# EDAv0_2.net
KiCad netlist of a schematic drawn in EasyEDA Pro
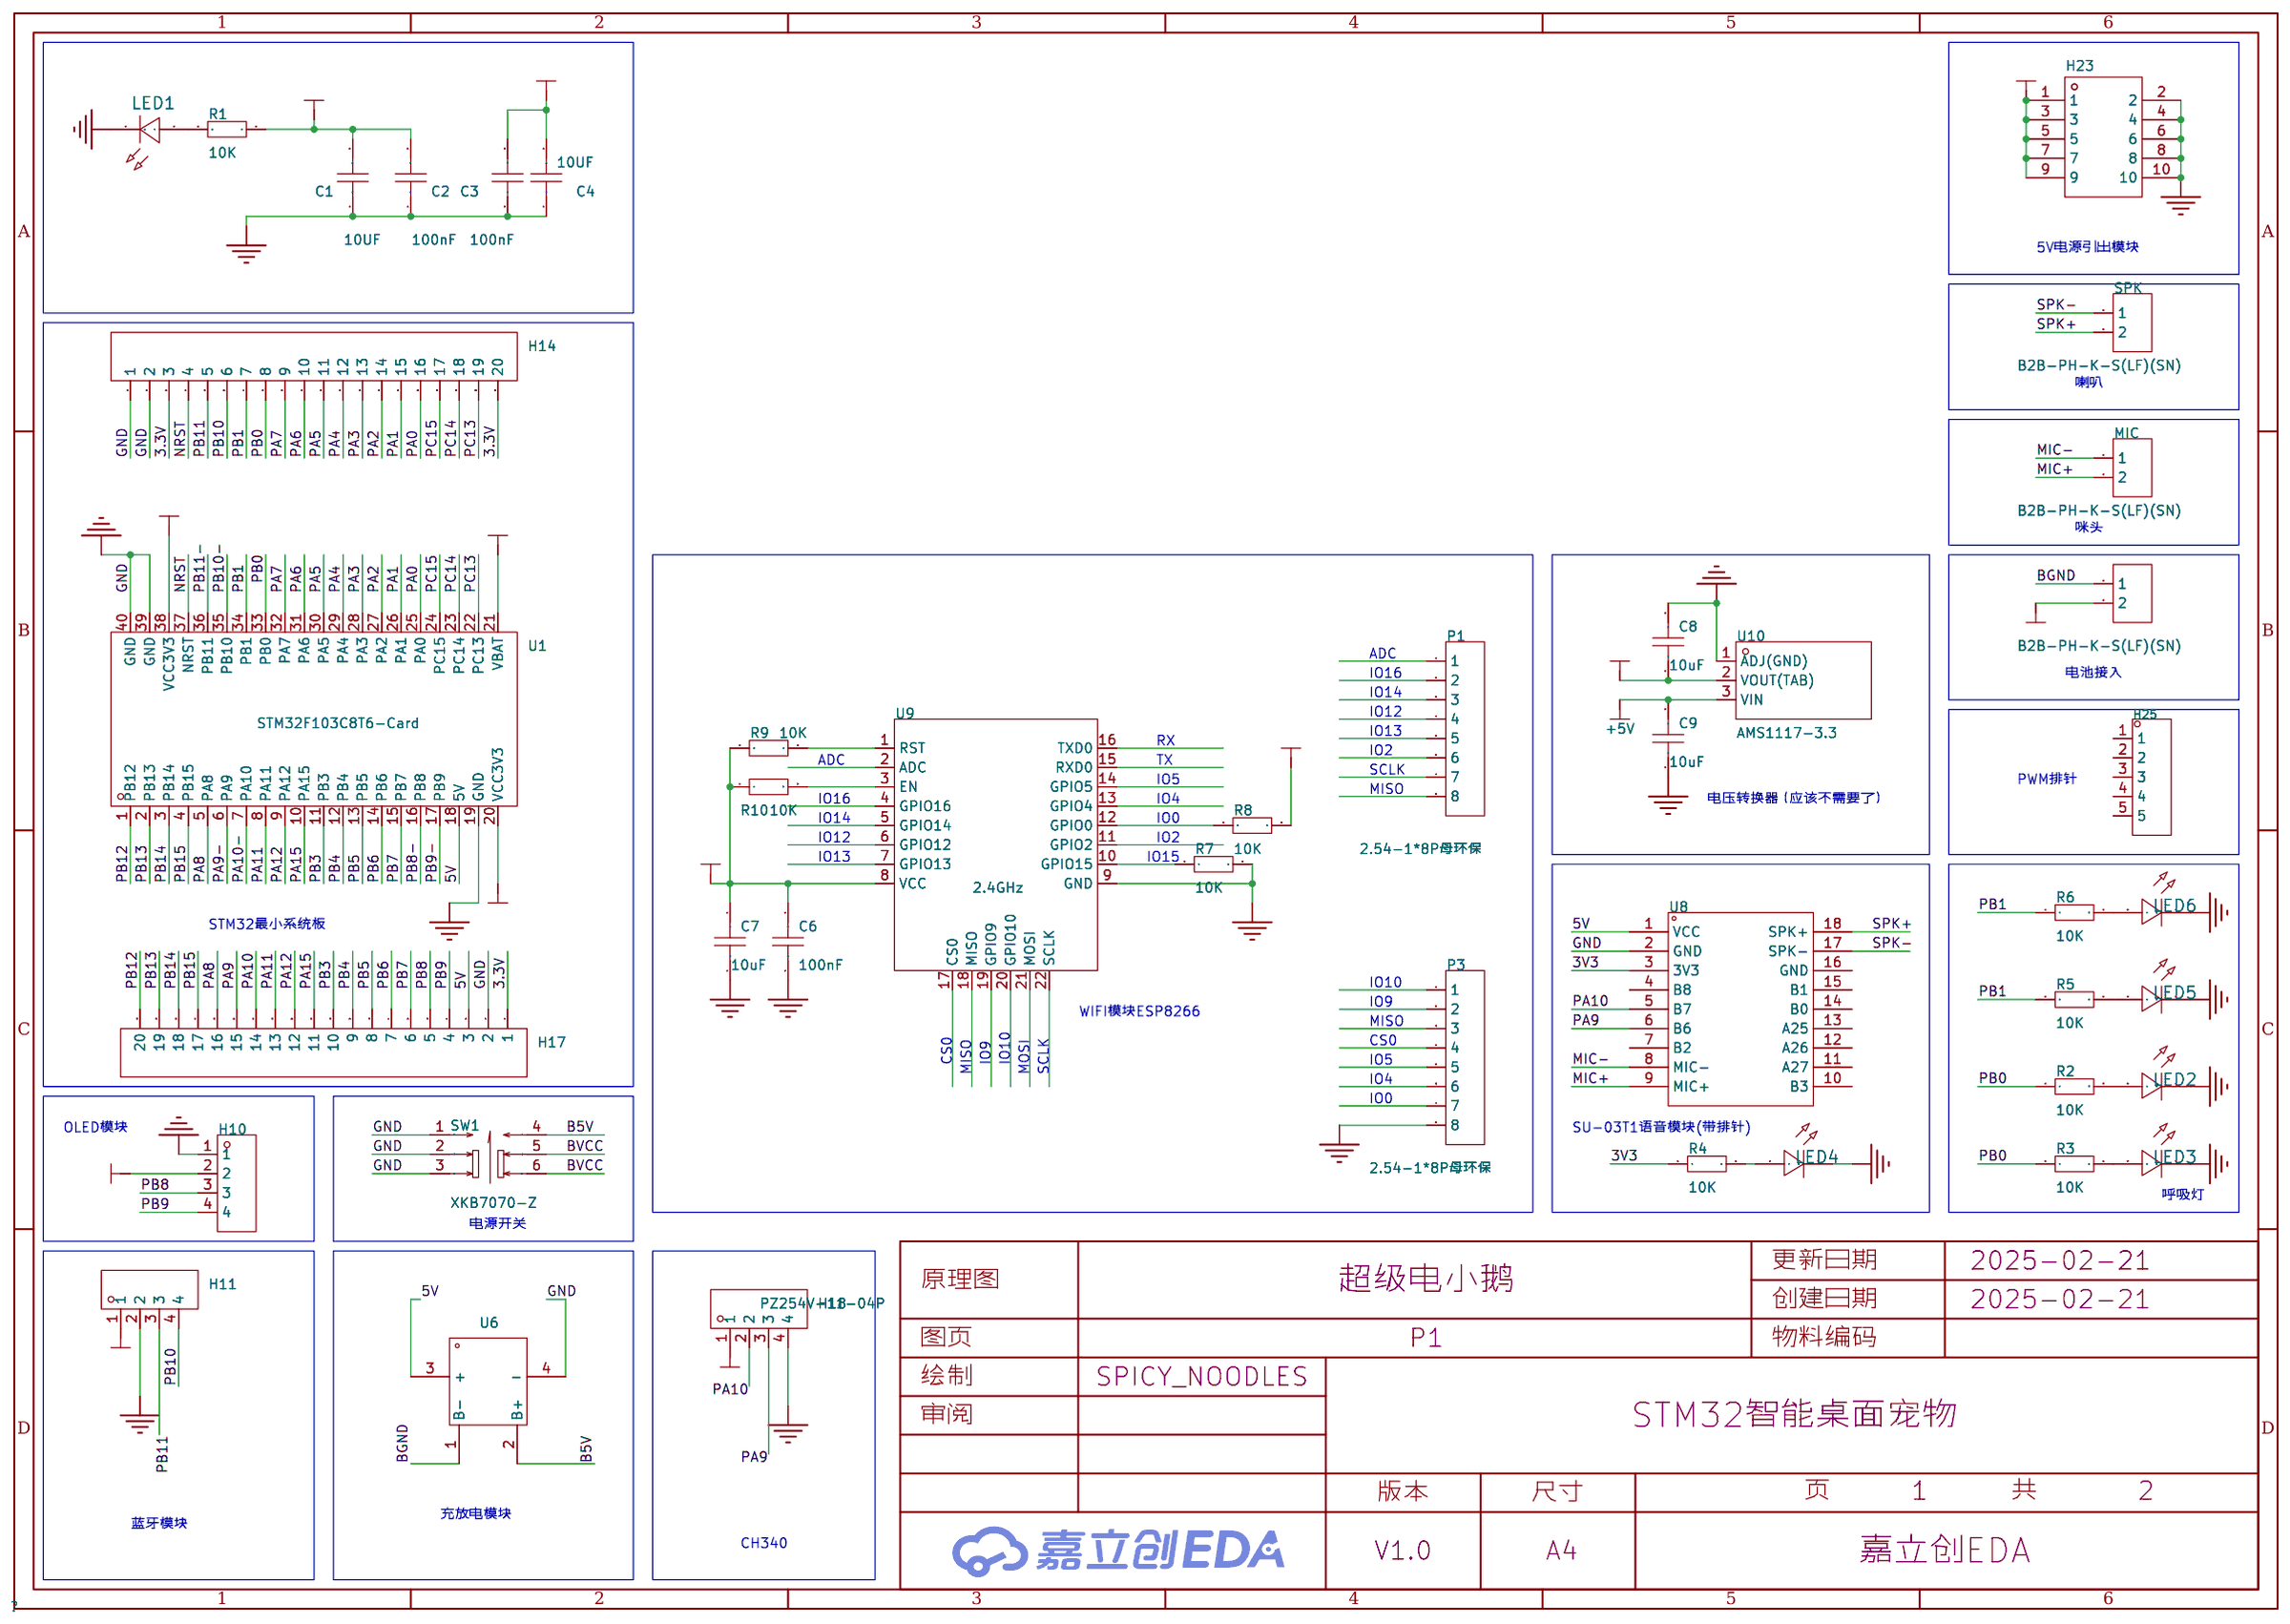
[diagram p0: schematic sheet]

(export (version "E")
  (design (tool "Eeschema 10.0.6"))
  (components
    (comp (ref "Battery")
      (value "B2B-PH-K-S(LF)(SN)")
      (footprint "easyedapro:HDR-TH_2P-P2.54-V-F")
      (fields (field (name "Manufacturer") "JST"))
      (libsource (lib "easyedapro") (part "Header-Female-2.54_1x2"))
    )
    (comp (ref "C1")
      (value "10UF")
      (footprint "easyedapro:C0805")
      (libsource (lib "easyedapro") (part "CapAcitance"))
    )
    (comp (ref "C2")
      (value "100nF")
      (footprint "easyedapro:C0805")
      (libsource (lib "easyedapro") (part "CapAcitance"))
    )
    (comp (ref "C3")
      (value "100nF")
      (footprint "easyedapro:C0805")
      (libsource (lib "easyedapro") (part "CapAcitance"))
    )
    (comp (ref "C4")
      (value "10UF")
      (footprint "easyedapro:C0805")
      (libsource (lib "easyedapro") (part "CapAcitance"))
    )
    (comp (ref "C6")
      (value "100nF")
      (footprint "easyedapro:C0805")
      (libsource (lib "easyedapro") (part "CapAcitance"))
    )
    (comp (ref "C7")
      (value "10uF")
      (footprint "easyedapro:C0603")
      (description "容值:10uF;精度:±10%;额定电压:10V;材质(温度系数):X5R;")
      (fields
        (field (name "Manufacturer Part") "CGA0603X5R106K100JT")
        (field (name "Manufacturer") "HRE(芯声)")
      )
      (libsource (lib "easyedapro") (part "CGA0603X5R106K100JT"))
    )
    (comp (ref "C8")
      (value "10uF")
      (footprint "easyedapro:C0603")
      (description "容值:10uF;精度:±10%;额定电压:10V;材质(温度系数):X5R;")
      (fields
        (field (name "Manufacturer Part") "CGA0603X5R106K100JT")
        (field (name "Manufacturer") "HRE(芯声)")
      )
      (libsource (lib "easyedapro") (part "CGA0603X5R106K100JT"))
    )
    (comp (ref "C9")
      (value "10uF")
      (footprint "easyedapro:C0603")
      (description "容值:10uF;精度:±10%;额定电压:10V;材质(温度系数):X5R;")
      (fields
        (field (name "Manufacturer Part") "CGA0603X5R106K100JT")
        (field (name "Manufacturer") "HRE(芯声)")
      )
      (libsource (lib "easyedapro") (part "CGA0603X5R106K100JT"))
    )
    (comp (ref "H10")
      (value "~")
      (footprint "easyedapro:HDR-TH_4P-P2.54-V-F")
      (libsource (lib "easyedapro") (part "2.54-1*4P母"))
    )
    (comp (ref "H11")
      (value "~")
      (footprint "easyedapro:HDR-TH_4P-P2.54-V-F")
      (libsource (lib "easyedapro") (part "2.54-1*4P母"))
    )
    (comp (ref "H14")
      (value "~")
      (footprint "easyedapro:HDR-TH_20P-P2.54-V-F")
      (libsource (lib "easyedapro") (part "HDR-F_2.54_1x20P"))
    )
    (comp (ref "H17")
      (value "~")
      (footprint "easyedapro:HDR-TH_20P-P2.54-V-F")
      (libsource (lib "easyedapro") (part "HDR-F_2.54_1x20P"))
    )
    (comp (ref "H18")
      (value "PZ254V-11-04P")
      (footprint "easyedapro:HDR-TH_4P-P2.54-V-F")
      (fields (field (name "Manufacturer") "XFCN(兴飞)"))
      (libsource (lib "easyedapro") (part "2.54-1*4P母"))
    )
    (comp (ref "H23")
      (value "~")
      (footprint "easyedapro:HDR-TH_10P-P2.54-V-M-R2-C5-S2.54")
      (libsource (lib "easyedapro") (part "HDR-M-2.54_2x5"))
    )
    (comp (ref "H25")
      (value "~")
      (footprint "easyedapro:HDR-TH_5P-P2.54-V-M")
      (libsource (lib "easyedapro") (part "MTP125-1105S1"))
    )
    (comp (ref "LED1")
      (value "~")
      (footprint "easyedapro:LED_0805")
      (libsource (lib "easyedapro") (part "LED_R"))
    )
    (comp (ref "LED2")
      (value "~")
      (footprint "easyedapro:LED_0805")
      (libsource (lib "easyedapro") (part "LED_R"))
    )
    (comp (ref "LED3")
      (value "~")
      (footprint "easyedapro:LED_0805")
      (libsource (lib "easyedapro") (part "LED_R"))
    )
    (comp (ref "LED4")
      (value "~")
      (footprint "easyedapro:LED_0805")
      (libsource (lib "easyedapro") (part "LED_R"))
    )
    (comp (ref "LED5")
      (value "~")
      (footprint "easyedapro:LED_0805")
      (libsource (lib "easyedapro") (part "LED_R"))
    )
    (comp (ref "LED6")
      (value "~")
      (footprint "easyedapro:LED_0805")
      (libsource (lib "easyedapro") (part "LED_R"))
    )
    (comp (ref "MIC")
      (value "B2B-PH-K-S(LF)(SN)")
      (footprint "easyedapro:HDR-TH_2P-P2.54-V-F")
      (fields (field (name "Manufacturer") "JST"))
      (libsource (lib "easyedapro") (part "Header-Female-2.54_1x2"))
    )
    (comp (ref "P1")
      (value "2.54-1*8P母环保")
      (footprint "easyedapro:HDR-TH_8P-P2.54-V-F-1")
      (description "插孔结构:1x8P;间距:2.54mm;行距:-;安装类型:直插;排数:单排;总孔位数:8P;塑高:-;触头材质:-;触头镀层:-;")
      (fields (field (name "Manufacturer") "BOOMELE(博穆精密)"))
      (libsource (lib "easyedapro") (part "Header-Female-2.54_1x8"))
    )
    (comp (ref "P3")
      (value "2.54-1*8P母环保")
      (footprint "easyedapro:HDR-TH_8P-P2.54-V-F-1")
      (description "插孔结构:1x8P;间距:2.54mm;行距:-;安装类型:直插;排数:单排;总孔位数:8P;塑高:-;触头材质:-;触头镀层:-;")
      (fields (field (name "Manufacturer") "BOOMELE(博穆精密)"))
      (libsource (lib "easyedapro") (part "Header-Female-2.54_1x8"))
    )
    (comp (ref "R1") (value "10K") (footprint "easyedapro:R0805") (libsource (lib "easyedapro") (part "电阻")))
    (comp (ref "R2") (value "10K") (footprint "easyedapro:R0805") (libsource (lib "easyedapro") (part "电阻")))
    (comp (ref "R3") (value "10K") (footprint "easyedapro:R0805") (libsource (lib "easyedapro") (part "电阻")))
    (comp (ref "R4") (value "10K") (footprint "easyedapro:R0805") (libsource (lib "easyedapro") (part "电阻")))
    (comp (ref "R5") (value "10K") (footprint "easyedapro:R0805") (libsource (lib "easyedapro") (part "电阻")))
    (comp (ref "R6") (value "10K") (footprint "easyedapro:R0805") (libsource (lib "easyedapro") (part "电阻")))
    (comp (ref "R7") (value "10K") (footprint "easyedapro:R0805") (libsource (lib "easyedapro") (part "电阻")))
    (comp (ref "R8") (value "10K") (footprint "easyedapro:R0805") (libsource (lib "easyedapro") (part "电阻")))
    (comp (ref "R9") (value "10K") (footprint "easyedapro:R0805") (libsource (lib "easyedapro") (part "电阻")))
    (comp (ref "R10") (value "10K") (footprint "easyedapro:R0805") (libsource (lib "easyedapro") (part "电阻")))
    (comp (ref "SPK")
      (value "B2B-PH-K-S(LF)(SN)")
      (footprint "easyedapro:HDR-TH_2P-P2.54-V-F")
      (fields (field (name "Manufacturer") "JST"))
      (libsource (lib "easyedapro") (part "Header-Female-2.54_1x2"))
    )
    (comp (ref "SW1")
      (value "XKB7070-Z")
      (footprint "easyedapro:SW-TH_6P-L7.0-W7.0-P2.00")
      (description "自锁/无锁:自锁;安装方式:直插;触点电流:100mA;额定电压 (AC):250V;额定电压 (DC):30V;带灯:不带;作用力:160gf;机械寿命:10万次;")
      (fields (field (name "Manufacturer") "XKB Connectivity(中国星坤)"))
      (libsource (lib "easyedapro") (part "XKB7070-Z"))
    )
    (comp (ref "U1")
      (value "STM32F103C8T6-Card")
      (footprint "easyedapro:CONN-TH_L53.3-W22.9_STM32F103C8T6-CARD")
      (libsource (lib "easyedapro") (part "STM32F103C8T6-CARD"))
    )
    (comp (ref "U6") (value "~") (libsource (lib "easyedapro") (part "5V充放电模块")))
    (comp (ref "U8")
      (value "~")
      (footprint "easyedapro:SU-03T带排针")
      (libsource (lib "easyedapro") (part "SU-03T带排针"))
    )
    (comp (ref "U9")
      (value "2.4GHz")
      (footprint "easyedapro:WIFIM-SMD_ESP-12F-ESP8266MOD")
      (description "核心处理器:ESP8266芯片;频率:2.4GHz;天线形式:板载PCB天线;发射功率:16dBm;接收灵敏度:-90dBm;")
      (fields
        (field (name "Manufacturer Part") "ESP-12F(ESP8266MOD)")
        (field (name "Manufacturer") "Ai-Thinker(安信可)")
      )
      (libsource (lib "easyedapro") (part "ESP-12F(ESP8266MOD)"))
    )
    (comp (ref "U10")
      (value "AMS1117-3.3")
      (footprint "easyedapro:SOT-89_L4.5-W2.5-P1.50-LS4.2-BR")
      (description "输出类型:固定;工作电压:18V;输出电压:3.3V;输出电流:1A;电源纹波抑制比(PSRR):60dB@(120Hz);输出极性:正极;")
      (fields (field (name "Manufacturer") "UMW(友台半导体)"))
      (libsource (lib "easyedapro") (part "AMS1117-3.3_C347256"))
    )
  )
  (nets
    (net (code "1") (name "+5V") (class "Default")
      (node (ref "C9") (pin "2") (pinfunction "2_2") (pintype "unspecified"))
      (node (ref "U10") (pin "3") (pinfunction "VIN_3") (pintype "unspecified"))
    )
    (net (code "2") (name "/3V3") (class "Default")
      (node (ref "R4") (pin "1") (pinfunction "1_1") (pintype "input"))
      (node (ref "U8") (pin "3") (pinfunction "3V3_3") (pintype "input"))
    )
    (net (code "3") (name "/B5V") (class "Default")
      (node (ref "SW1") (pin "4") (pinfunction "4_4") (pintype "unspecified"))
      (node (ref "U6") (pin "2") (pinfunction "B+_2") (pintype "input"))
    )
    (net (code "4") (name "/BGND") (class "Default")
      (node (ref "Battery") (pin "1") (pinfunction "1_1") (pintype "input"))
      (node (ref "U6") (pin "1") (pinfunction "B-_1") (pintype "input"))
    )
    (net (code "5") (name "/MIC+") (class "Default")
      (node (ref "MIC") (pin "2") (pinfunction "2_2") (pintype "input"))
      (node (ref "U8") (pin "9") (pinfunction "MIC+_9") (pintype "input"))
    )
    (net (code "6") (name "/MIC-") (class "Default")
      (node (ref "MIC") (pin "1") (pinfunction "1_1") (pintype "input"))
      (node (ref "U8") (pin "8") (pinfunction "MIC-_8") (pintype "input"))
    )
    (net (code "7") (name "/NRST") (class "Default")
      (node (ref "H14") (pin "4") (pinfunction "4_4") (pintype "input"))
      (node (ref "U1") (pin "37") (pinfunction "NRST_37") (pintype "unspecified"))
    )
    (net (code "8") (name "/PA0") (class "Default")
      (node (ref "H14") (pin "16") (pinfunction "16_16") (pintype "input"))
      (node (ref "U1") (pin "25") (pinfunction "PA0_25") (pintype "unspecified"))
    )
    (net (code "9") (name "/PA1") (class "Default")
      (node (ref "H14") (pin "15") (pinfunction "15_15") (pintype "input"))
      (node (ref "U1") (pin "26") (pinfunction "PA1_26") (pintype "unspecified"))
    )
    (net (code "10") (name "/PA2") (class "Default")
      (node (ref "H14") (pin "14") (pinfunction "14_14") (pintype "input"))
      (node (ref "U1") (pin "27") (pinfunction "PA2_27") (pintype "unspecified"))
    )
    (net (code "11") (name "/PA3") (class "Default")
      (node (ref "H14") (pin "13") (pinfunction "13_13") (pintype "input"))
      (node (ref "U1") (pin "28") (pinfunction "PA3_28") (pintype "unspecified"))
    )
    (net (code "12") (name "/PA4") (class "Default")
      (node (ref "H14") (pin "12") (pinfunction "12_12") (pintype "input"))
      (node (ref "U1") (pin "29") (pinfunction "PA4_29") (pintype "unspecified"))
    )
    (net (code "13") (name "/PA5") (class "Default")
      (node (ref "H14") (pin "11") (pinfunction "11_11") (pintype "input"))
      (node (ref "U1") (pin "30") (pinfunction "PA5_30") (pintype "unspecified"))
    )
    (net (code "14") (name "/PA6") (class "Default")
      (node (ref "H14") (pin "10") (pinfunction "10_10") (pintype "input"))
      (node (ref "U1") (pin "31") (pinfunction "PA6_31") (pintype "unspecified"))
    )
    (net (code "15") (name "/PA7") (class "Default")
      (node (ref "H14") (pin "9") (pinfunction "9_9") (pintype "input"))
      (node (ref "U1") (pin "32") (pinfunction "PA7_32") (pintype "unspecified"))
    )
    (net (code "16") (name "/PA8") (class "Default")
      (node (ref "H17") (pin "16") (pinfunction "16_16") (pintype "input"))
      (node (ref "U1") (pin "5") (pinfunction "PA8_5") (pintype "unspecified"))
    )
    (net (code "17") (name "/PA9") (class "Default")
      (node (ref "H17") (pin "15") (pinfunction "15_15") (pintype "input"))
      (node (ref "H18") (pin "3") (pinfunction "3_3") (pintype "unspecified"))
      (node (ref "U8") (pin "6") (pinfunction "B6_6") (pintype "input"))
    )
    (net (code "18") (name "/PA9-") (class "Default")
      (node (ref "U1") (pin "6") (pinfunction "PA9_6") (pintype "unspecified"))
    )
    (net (code "19") (name "/PA10") (class "Default")
      (node (ref "H17") (pin "14") (pinfunction "14_14") (pintype "input"))
      (node (ref "H18") (pin "2") (pinfunction "2_2") (pintype "unspecified"))
      (node (ref "U8") (pin "5") (pinfunction "B7_5") (pintype "input"))
    )
    (net (code "20") (name "/PA10-") (class "Default")
      (node (ref "U1") (pin "7") (pinfunction "PA10_7") (pintype "unspecified"))
    )
    (net (code "21") (name "/PA11") (class "Default")
      (node (ref "H17") (pin "13") (pinfunction "13_13") (pintype "input"))
      (node (ref "U1") (pin "8") (pinfunction "PA11_8") (pintype "unspecified"))
    )
    (net (code "22") (name "/PA12") (class "Default")
      (node (ref "H17") (pin "12") (pinfunction "12_12") (pintype "input"))
      (node (ref "U1") (pin "9") (pinfunction "PA12_9") (pintype "unspecified"))
    )
    (net (code "23") (name "/PA15") (class "Default")
      (node (ref "H17") (pin "11") (pinfunction "11_11") (pintype "input"))
      (node (ref "U1") (pin "10") (pinfunction "PA15_10") (pintype "unspecified"))
    )
    (net (code "24") (name "/PB0") (class "Default")
      (node (ref "H14") (pin "8") (pinfunction "8_8") (pintype "input"))
      (node (ref "R2") (pin "1") (pinfunction "1_1") (pintype "input"))
      (node (ref "R3") (pin "1") (pinfunction "1_1") (pintype "input"))
      (node (ref "U1") (pin "33") (pinfunction "PB0_33") (pintype "unspecified"))
    )
    (net (code "25") (name "/PB1") (class "Default")
      (node (ref "H14") (pin "7") (pinfunction "7_7") (pintype "input"))
      (node (ref "R5") (pin "1") (pinfunction "1_1") (pintype "input"))
      (node (ref "R6") (pin "1") (pinfunction "1_1") (pintype "input"))
      (node (ref "U1") (pin "34") (pinfunction "PB1_34") (pintype "unspecified"))
    )
    (net (code "26") (name "/PB3") (class "Default")
      (node (ref "H17") (pin "10") (pinfunction "10_10") (pintype "input"))
      (node (ref "U1") (pin "11") (pinfunction "PB3_11") (pintype "unspecified"))
    )
    (net (code "27") (name "/PB4") (class "Default")
      (node (ref "H17") (pin "9") (pinfunction "9_9") (pintype "input"))
      (node (ref "U1") (pin "12") (pinfunction "PB4_12") (pintype "unspecified"))
    )
    (net (code "28") (name "/PB5") (class "Default")
      (node (ref "H17") (pin "8") (pinfunction "8_8") (pintype "input"))
      (node (ref "U1") (pin "13") (pinfunction "PB5_13") (pintype "unspecified"))
    )
    (net (code "29") (name "/PB6") (class "Default")
      (node (ref "H17") (pin "7") (pinfunction "7_7") (pintype "input"))
      (node (ref "U1") (pin "14") (pinfunction "PB6_14") (pintype "unspecified"))
    )
    (net (code "30") (name "/PB7") (class "Default")
      (node (ref "H17") (pin "6") (pinfunction "6_6") (pintype "input"))
      (node (ref "U1") (pin "15") (pinfunction "PB7_15") (pintype "unspecified"))
    )
    (net (code "31") (name "/PB8") (class "Default")
      (node (ref "H10") (pin "3") (pinfunction "3_3") (pintype "unspecified"))
      (node (ref "H17") (pin "5") (pinfunction "5_5") (pintype "input"))
    )
    (net (code "32") (name "/PB8-") (class "Default")
      (node (ref "U1") (pin "16") (pinfunction "PB8_16") (pintype "unspecified"))
    )
    (net (code "33") (name "/PB9") (class "Default")
      (node (ref "H10") (pin "4") (pinfunction "4_4") (pintype "unspecified"))
      (node (ref "H17") (pin "4") (pinfunction "4_4") (pintype "input"))
    )
    (net (code "34") (name "/PB9-") (class "Default")
      (node (ref "U1") (pin "17") (pinfunction "PB9_17") (pintype "unspecified"))
    )
    (net (code "35") (name "/PB10") (class "Default")
      (node (ref "H11") (pin "4") (pinfunction "4_4") (pintype "unspecified"))
      (node (ref "H14") (pin "6") (pinfunction "6_6") (pintype "input"))
    )
    (net (code "36") (name "/PB10-") (class "Default")
      (node (ref "U1") (pin "35") (pinfunction "PB10_35") (pintype "unspecified"))
    )
    (net (code "37") (name "/PB11") (class "Default")
      (node (ref "H11") (pin "3") (pinfunction "3_3") (pintype "unspecified"))
      (node (ref "H14") (pin "5") (pinfunction "5_5") (pintype "input"))
    )
    (net (code "38") (name "/PB11-") (class "Default")
      (node (ref "U1") (pin "36") (pinfunction "PB11_36") (pintype "unspecified"))
    )
    (net (code "39") (name "/PB12") (class "Default")
      (node (ref "H17") (pin "20") (pinfunction "20_20") (pintype "input"))
      (node (ref "U1") (pin "1") (pinfunction "PB12_1") (pintype "unspecified"))
    )
    (net (code "40") (name "/PB13") (class "Default")
      (node (ref "H17") (pin "19") (pinfunction "19_19") (pintype "input"))
      (node (ref "U1") (pin "2") (pinfunction "PB13_2") (pintype "unspecified"))
    )
    (net (code "41") (name "/PB14") (class "Default")
      (node (ref "H17") (pin "18") (pinfunction "18_18") (pintype "input"))
      (node (ref "U1") (pin "3") (pinfunction "PB14_3") (pintype "unspecified"))
    )
    (net (code "42") (name "/PB15") (class "Default")
      (node (ref "H17") (pin "17") (pinfunction "17_17") (pintype "input"))
      (node (ref "U1") (pin "4") (pinfunction "PB15_4") (pintype "unspecified"))
    )
    (net (code "43") (name "/PC13") (class "Default")
      (node (ref "H14") (pin "19") (pinfunction "19_19") (pintype "input"))
      (node (ref "U1") (pin "22") (pinfunction "PC13_22") (pintype "unspecified"))
    )
    (net (code "44") (name "/PC14") (class "Default")
      (node (ref "H14") (pin "18") (pinfunction "18_18") (pintype "input"))
      (node (ref "U1") (pin "23") (pinfunction "PC14_23") (pintype "unspecified"))
    )
    (net (code "45") (name "/PC15") (class "Default")
      (node (ref "H14") (pin "17") (pinfunction "17_17") (pintype "input"))
      (node (ref "U1") (pin "24") (pinfunction "PC15_24") (pintype "unspecified"))
    )
    (net (code "46") (name "/SPK+") (class "Default")
      (node (ref "SPK") (pin "2") (pinfunction "2_2") (pintype "input"))
      (node (ref "U8") (pin "18") (pinfunction "SPK+_18") (pintype "input"))
    )
    (net (code "47") (name "/SPK-") (class "Default")
      (node (ref "SPK") (pin "1") (pinfunction "1_1") (pintype "input"))
      (node (ref "U8") (pin "17") (pinfunction "SPK-_17") (pintype "input"))
    )
    (net (code "48") (name "3.3V") (class "Default")
      (node (ref "C3") (pin "2") (pinfunction "2_2") (pintype "input"))
      (node (ref "C4") (pin "2") (pinfunction "2_2") (pintype "input"))
      (node (ref "C6") (pin "2") (pinfunction "2_2") (pintype "input"))
      (node (ref "C7") (pin "2") (pinfunction "2_2") (pintype "unspecified"))
      (node (ref "C8") (pin "1") (pinfunction "1_1") (pintype "unspecified"))
      (node (ref "H10") (pin "2") (pinfunction "2_2") (pintype "unspecified"))
      (node (ref "H11") (pin "1") (pinfunction "1_1") (pintype "unspecified"))
      (node (ref "H14") (pin "20") (pinfunction "20_20") (pintype "input"))
      (node (ref "H14") (pin "3") (pinfunction "3_3") (pintype "input"))
      (node (ref "H17") (pin "1") (pinfunction "1_1") (pintype "input"))
      (node (ref "R10") (pin "1") (pinfunction "1_1") (pintype "input"))
      (node (ref "R8") (pin "2") (pinfunction "2_2") (pintype "input"))
      (node (ref "R9") (pin "1") (pinfunction "1_1") (pintype "input"))
      (node (ref "U1") (pin "20") (pinfunction "VCC3V3_20") (pintype "unspecified"))
      (node (ref "U1") (pin "21") (pinfunction "VBAT_21") (pintype "unspecified"))
      (node (ref "U1") (pin "38") (pinfunction "VCC3V3_38") (pintype "unspecified"))
      (node (ref "U10") (pin "2") (pinfunction "VOUT(TAB)_2") (pintype "unspecified"))
      (node (ref "U9") (pin "8") (pinfunction "VCC_8") (pintype "unspecified"))
    )
    (net (code "49") (name "5V") (class "Default")
      (node (ref "C1") (pin "2") (pinfunction "2_2") (pintype "input"))
      (node (ref "C2") (pin "2") (pinfunction "2_2") (pintype "input"))
      (node (ref "H17") (pin "3") (pinfunction "3_3") (pintype "input"))
      (node (ref "H18") (pin "1") (pinfunction "1_1") (pintype "unspecified"))
      (node (ref "H23") (pin "1") (pinfunction "1_1") (pintype "input"))
      (node (ref "H23") (pin "3") (pinfunction "3_3") (pintype "input"))
      (node (ref "H23") (pin "5") (pinfunction "5_5") (pintype "input"))
      (node (ref "H23") (pin "7") (pinfunction "7_7") (pintype "input"))
      (node (ref "H23") (pin "9") (pinfunction "9_9") (pintype "input"))
      (node (ref "R1") (pin "1") (pinfunction "1_1") (pintype "input"))
      (node (ref "U1") (pin "18") (pinfunction "5V_18") (pintype "unspecified"))
      (node (ref "U6") (pin "3") (pinfunction "+_3") (pintype "input"))
      (node (ref "U8") (pin "1") (pinfunction "VCC_1") (pintype "input"))
    )
    (net (code "50") (name "BVCC") (class "Default")
      (node (ref "Battery") (pin "2") (pinfunction "2_2") (pintype "input"))
      (node (ref "SW1") (pin "5") (pinfunction "5_5") (pintype "unspecified"))
      (node (ref "SW1") (pin "6") (pinfunction "6_6") (pintype "unspecified"))
    )
    (net (code "51") (name "GND") (class "Default")
      (node (ref "C1") (pin "1") (pinfunction "1_1") (pintype "input"))
      (node (ref "C2") (pin "1") (pinfunction "1_1") (pintype "input"))
      (node (ref "C3") (pin "1") (pinfunction "1_1") (pintype "input"))
      (node (ref "C4") (pin "1") (pinfunction "1_1") (pintype "input"))
      (node (ref "C6") (pin "1") (pinfunction "1_1") (pintype "input"))
      (node (ref "C7") (pin "1") (pinfunction "1_1") (pintype "unspecified"))
      (node (ref "C8") (pin "2") (pinfunction "2_2") (pintype "unspecified"))
      (node (ref "C9") (pin "1") (pinfunction "1_1") (pintype "unspecified"))
      (node (ref "H10") (pin "1") (pinfunction "1_1") (pintype "unspecified"))
      (node (ref "H11") (pin "2") (pinfunction "2_2") (pintype "unspecified"))
      (node (ref "H14") (pin "1") (pinfunction "1_1") (pintype "input"))
      (node (ref "H14") (pin "2") (pinfunction "2_2") (pintype "input"))
      (node (ref "H17") (pin "2") (pinfunction "2_2") (pintype "input"))
      (node (ref "H18") (pin "4") (pinfunction "4_4") (pintype "unspecified"))
      (node (ref "H23") (pin "10") (pinfunction "10_10") (pintype "input"))
      (node (ref "H23") (pin "2") (pinfunction "2_2") (pintype "input"))
      (node (ref "H23") (pin "4") (pinfunction "4_4") (pintype "input"))
      (node (ref "H23") (pin "6") (pinfunction "6_6") (pintype "input"))
      (node (ref "H23") (pin "8") (pinfunction "8_8") (pintype "input"))
      (node (ref "LED1") (pin "1") (pinfunction "C_1") (pintype "input"))
      (node (ref "LED2") (pin "1") (pinfunction "C_1") (pintype "input"))
      (node (ref "LED3") (pin "1") (pinfunction "C_1") (pintype "input"))
      (node (ref "LED4") (pin "1") (pinfunction "C_1") (pintype "input"))
      (node (ref "LED5") (pin "1") (pinfunction "C_1") (pintype "input"))
      (node (ref "LED6") (pin "1") (pinfunction "C_1") (pintype "input"))
      (node (ref "P3") (pin "8") (pinfunction "8_8") (pintype "input"))
      (node (ref "R7") (pin "2") (pinfunction "2_2") (pintype "input"))
      (node (ref "SW1") (pin "1") (pinfunction "1_1") (pintype "unspecified"))
      (node (ref "SW1") (pin "2") (pinfunction "2_2") (pintype "unspecified"))
      (node (ref "SW1") (pin "3") (pinfunction "3_3") (pintype "unspecified"))
      (node (ref "U1") (pin "19") (pinfunction "GND_19") (pintype "unspecified"))
      (node (ref "U1") (pin "39") (pinfunction "GND_39") (pintype "unspecified"))
      (node (ref "U1") (pin "40") (pinfunction "GND_40") (pintype "unspecified"))
      (node (ref "U10") (pin "1") (pinfunction "ADJ(GND)_1") (pintype "unspecified"))
      (node (ref "U6") (pin "4") (pinfunction "-_4") (pintype "input"))
      (node (ref "U8") (pin "2") (pinfunction "GND_2") (pintype "input"))
      (node (ref "U9") (pin "9") (pinfunction "GND_9") (pintype "unspecified"))
    )
    (net (code "52") (name "Net-(LED1-A)") (class "Default")
      (node (ref "LED1") (pin "2") (pinfunction "A_2") (pintype "input"))
      (node (ref "R1") (pin "2") (pinfunction "2_2") (pintype "input"))
    )
    (net (code "53") (name "Net-(LED2-A)") (class "Default")
      (node (ref "LED2") (pin "2") (pinfunction "A_2") (pintype "input"))
      (node (ref "R2") (pin "2") (pinfunction "2_2") (pintype "input"))
    )
    (net (code "54") (name "Net-(LED3-A)") (class "Default")
      (node (ref "LED3") (pin "2") (pinfunction "A_2") (pintype "input"))
      (node (ref "R3") (pin "2") (pinfunction "2_2") (pintype "input"))
    )
    (net (code "55") (name "Net-(LED4-A)") (class "Default")
      (node (ref "LED4") (pin "2") (pinfunction "A_2") (pintype "input"))
      (node (ref "R4") (pin "2") (pinfunction "2_2") (pintype "input"))
    )
    (net (code "56") (name "Net-(LED5-A)") (class "Default")
      (node (ref "LED5") (pin "2") (pinfunction "A_2") (pintype "input"))
      (node (ref "R5") (pin "2") (pinfunction "2_2") (pintype "input"))
    )
    (net (code "57") (name "Net-(LED6-A)") (class "Default")
      (node (ref "LED6") (pin "2") (pinfunction "A_2") (pintype "input"))
      (node (ref "R6") (pin "2") (pinfunction "2_2") (pintype "input"))
    )
    (net (code "58") (name "Net-(U9-EN)") (class "Default")
      (node (ref "R10") (pin "2") (pinfunction "2_2") (pintype "input"))
      (node (ref "U9") (pin "3") (pinfunction "EN_3") (pintype "unspecified"))
    )
    (net (code "59") (name "Net-(U9-GPIO0)") (class "Default")
      (node (ref "R8") (pin "1") (pinfunction "1_1") (pintype "input"))
      (node (ref "U9") (pin "12") (pinfunction "GPIO0_12") (pintype "unspecified"))
    )
    (net (code "60") (name "Net-(U9-GPIO15)") (class "Default")
      (node (ref "R7") (pin "1") (pinfunction "1_1") (pintype "input"))
      (node (ref "U9") (pin "10") (pinfunction "GPIO15_10") (pintype "unspecified"))
    )
    (net (code "61") (name "Net-(U9-RST)") (class "Default")
      (node (ref "R9") (pin "2") (pinfunction "2_2") (pintype "input"))
      (node (ref "U9") (pin "1") (pinfunction "RST_1") (pintype "unspecified"))
    )
    (net (code "62") (name "unconnected-(H25-Pad1)") (class "Default")
      (node (ref "H25") (pin "1") (pinfunction "1_1") (pintype "input"))
    )
    (net (code "63") (name "unconnected-(H25-Pad2)") (class "Default")
      (node (ref "H25") (pin "2") (pinfunction "2_2") (pintype "input"))
    )
    (net (code "64") (name "unconnected-(H25-Pad3)") (class "Default")
      (node (ref "H25") (pin "3") (pinfunction "3_3") (pintype "input"))
    )
    (net (code "65") (name "unconnected-(H25-Pad4)") (class "Default")
      (node (ref "H25") (pin "4") (pinfunction "4_4") (pintype "input"))
    )
    (net (code "66") (name "unconnected-(H25-Pad5)") (class "Default")
      (node (ref "H25") (pin "5") (pinfunction "5_5") (pintype "input"))
    )
    (net (code "67") (name "unconnected-(P1-Pad1)") (class "Default")
      (node (ref "P1") (pin "1") (pinfunction "1_1") (pintype "input"))
    )
    (net (code "68") (name "unconnected-(P1-Pad2)") (class "Default")
      (node (ref "P1") (pin "2") (pinfunction "2_2") (pintype "input"))
    )
    (net (code "69") (name "unconnected-(P1-Pad3)") (class "Default")
      (node (ref "P1") (pin "3") (pinfunction "3_3") (pintype "input"))
    )
    (net (code "70") (name "unconnected-(P1-Pad4)") (class "Default")
      (node (ref "P1") (pin "4") (pinfunction "4_4") (pintype "input"))
    )
    (net (code "71") (name "unconnected-(P1-Pad5)") (class "Default")
      (node (ref "P1") (pin "5") (pinfunction "5_5") (pintype "input"))
    )
    (net (code "72") (name "unconnected-(P1-Pad6)") (class "Default")
      (node (ref "P1") (pin "6") (pinfunction "6_6") (pintype "input"))
    )
    (net (code "73") (name "unconnected-(P1-Pad7)") (class "Default")
      (node (ref "P1") (pin "7") (pinfunction "7_7") (pintype "input"))
    )
    (net (code "74") (name "unconnected-(P1-Pad8)") (class "Default")
      (node (ref "P1") (pin "8") (pinfunction "8_8") (pintype "input"))
    )
    (net (code "75") (name "unconnected-(P3-Pad1)") (class "Default")
      (node (ref "P3") (pin "1") (pinfunction "1_1") (pintype "input"))
    )
    (net (code "76") (name "unconnected-(P3-Pad2)") (class "Default")
      (node (ref "P3") (pin "2") (pinfunction "2_2") (pintype "input"))
    )
    (net (code "77") (name "unconnected-(P3-Pad3)") (class "Default")
      (node (ref "P3") (pin "3") (pinfunction "3_3") (pintype "input"))
    )
    (net (code "78") (name "unconnected-(P3-Pad4)") (class "Default")
      (node (ref "P3") (pin "4") (pinfunction "4_4") (pintype "input"))
    )
    (net (code "79") (name "unconnected-(P3-Pad5)") (class "Default")
      (node (ref "P3") (pin "5") (pinfunction "5_5") (pintype "input"))
    )
    (net (code "80") (name "unconnected-(P3-Pad6)") (class "Default")
      (node (ref "P3") (pin "6") (pinfunction "6_6") (pintype "input"))
    )
    (net (code "81") (name "unconnected-(P3-Pad7)") (class "Default")
      (node (ref "P3") (pin "7") (pinfunction "7_7") (pintype "input"))
    )
    (net (code "82") (name "unconnected-(U8-A25-Pad13)") (class "Default")
      (node (ref "U8") (pin "13") (pinfunction "A25_13") (pintype "input"))
    )
    (net (code "83") (name "unconnected-(U8-A26-Pad12)") (class "Default")
      (node (ref "U8") (pin "12") (pinfunction "A26_12") (pintype "input"))
    )
    (net (code "84") (name "unconnected-(U8-A27-Pad11)") (class "Default")
      (node (ref "U8") (pin "11") (pinfunction "A27_11") (pintype "input"))
    )
    (net (code "85") (name "unconnected-(U8-B0-Pad14)") (class "Default")
      (node (ref "U8") (pin "14") (pinfunction "B0_14") (pintype "input"))
    )
    (net (code "86") (name "unconnected-(U8-B1-Pad15)") (class "Default")
      (node (ref "U8") (pin "15") (pinfunction "B1_15") (pintype "input"))
    )
    (net (code "87") (name "unconnected-(U8-B2-Pad7)") (class "Default")
      (node (ref "U8") (pin "7") (pinfunction "B2_7") (pintype "input"))
    )
    (net (code "88") (name "unconnected-(U8-B3-Pad10)") (class "Default")
      (node (ref "U8") (pin "10") (pinfunction "B3_10") (pintype "input"))
    )
    (net (code "89") (name "unconnected-(U8-B8-Pad4)") (class "Default")
      (node (ref "U8") (pin "4") (pinfunction "B8_4") (pintype "input"))
    )
    (net (code "90") (name "unconnected-(U8-GND-Pad16)") (class "Default")
      (node (ref "U8") (pin "16") (pinfunction "GND_16") (pintype "input"))
    )
    (net (code "91") (name "unconnected-(U9-ADC-Pad2)") (class "Default")
      (node (ref "U9") (pin "2") (pinfunction "ADC_2") (pintype "unspecified"))
    )
    (net (code "92") (name "unconnected-(U9-CS0-Pad17)") (class "Default")
      (node (ref "U9") (pin "17") (pinfunction "CS0_17") (pintype "unspecified"))
    )
    (net (code "93") (name "unconnected-(U9-GPIO2-Pad11)") (class "Default")
      (node (ref "U9") (pin "11") (pinfunction "GPIO2_11") (pintype "unspecified"))
    )
    (net (code "94") (name "unconnected-(U9-GPIO4-Pad13)") (class "Default")
      (node (ref "U9") (pin "13") (pinfunction "GPIO4_13") (pintype "unspecified"))
    )
    (net (code "95") (name "unconnected-(U9-GPIO5-Pad14)") (class "Default")
      (node (ref "U9") (pin "14") (pinfunction "GPIO5_14") (pintype "unspecified"))
    )
    (net (code "96") (name "unconnected-(U9-GPIO9-Pad19)") (class "Default")
      (node (ref "U9") (pin "19") (pinfunction "GPIO9_19") (pintype "unspecified"))
    )
    (net (code "97") (name "unconnected-(U9-GPIO10-Pad20)") (class "Default")
      (node (ref "U9") (pin "20") (pinfunction "GPIO10_20") (pintype "unspecified"))
    )
    (net (code "98") (name "unconnected-(U9-GPIO12-Pad6)") (class "Default")
      (node (ref "U9") (pin "6") (pinfunction "GPIO12_6") (pintype "unspecified"))
    )
    (net (code "99") (name "unconnected-(U9-GPIO13-Pad7)") (class "Default")
      (node (ref "U9") (pin "7") (pinfunction "GPIO13_7") (pintype "unspecified"))
    )
    (net (code "100") (name "unconnected-(U9-GPIO14-Pad5)") (class "Default")
      (node (ref "U9") (pin "5") (pinfunction "GPIO14_5") (pintype "unspecified"))
    )
    (net (code "101") (name "unconnected-(U9-GPIO16-Pad4)") (class "Default")
      (node (ref "U9") (pin "4") (pinfunction "GPIO16_4") (pintype "unspecified"))
    )
    (net (code "102") (name "unconnected-(U9-MISO-Pad18)") (class "Default")
      (node (ref "U9") (pin "18") (pinfunction "MISO_18") (pintype "unspecified"))
    )
    (net (code "103") (name "unconnected-(U9-MOSI-Pad21)") (class "Default")
      (node (ref "U9") (pin "21") (pinfunction "MOSI_21") (pintype "unspecified"))
    )
    (net (code "104") (name "unconnected-(U9-RXD0-Pad15)") (class "Default")
      (node (ref "U9") (pin "15") (pinfunction "RXD0_15") (pintype "unspecified"))
    )
    (net (code "105") (name "unconnected-(U9-SCLK-Pad22)") (class "Default")
      (node (ref "U9") (pin "22") (pinfunction "SCLK_22") (pintype "unspecified"))
    )
    (net (code "106") (name "unconnected-(U9-TXD0-Pad16)") (class "Default")
      (node (ref "U9") (pin "16") (pinfunction "TXD0_16") (pintype "unspecified"))
    )
  )
)
